# 10X_SD_CARD_READER_SCH_SHEET_2.net
KiCad netlist of a schematic drawn in Altium Designer
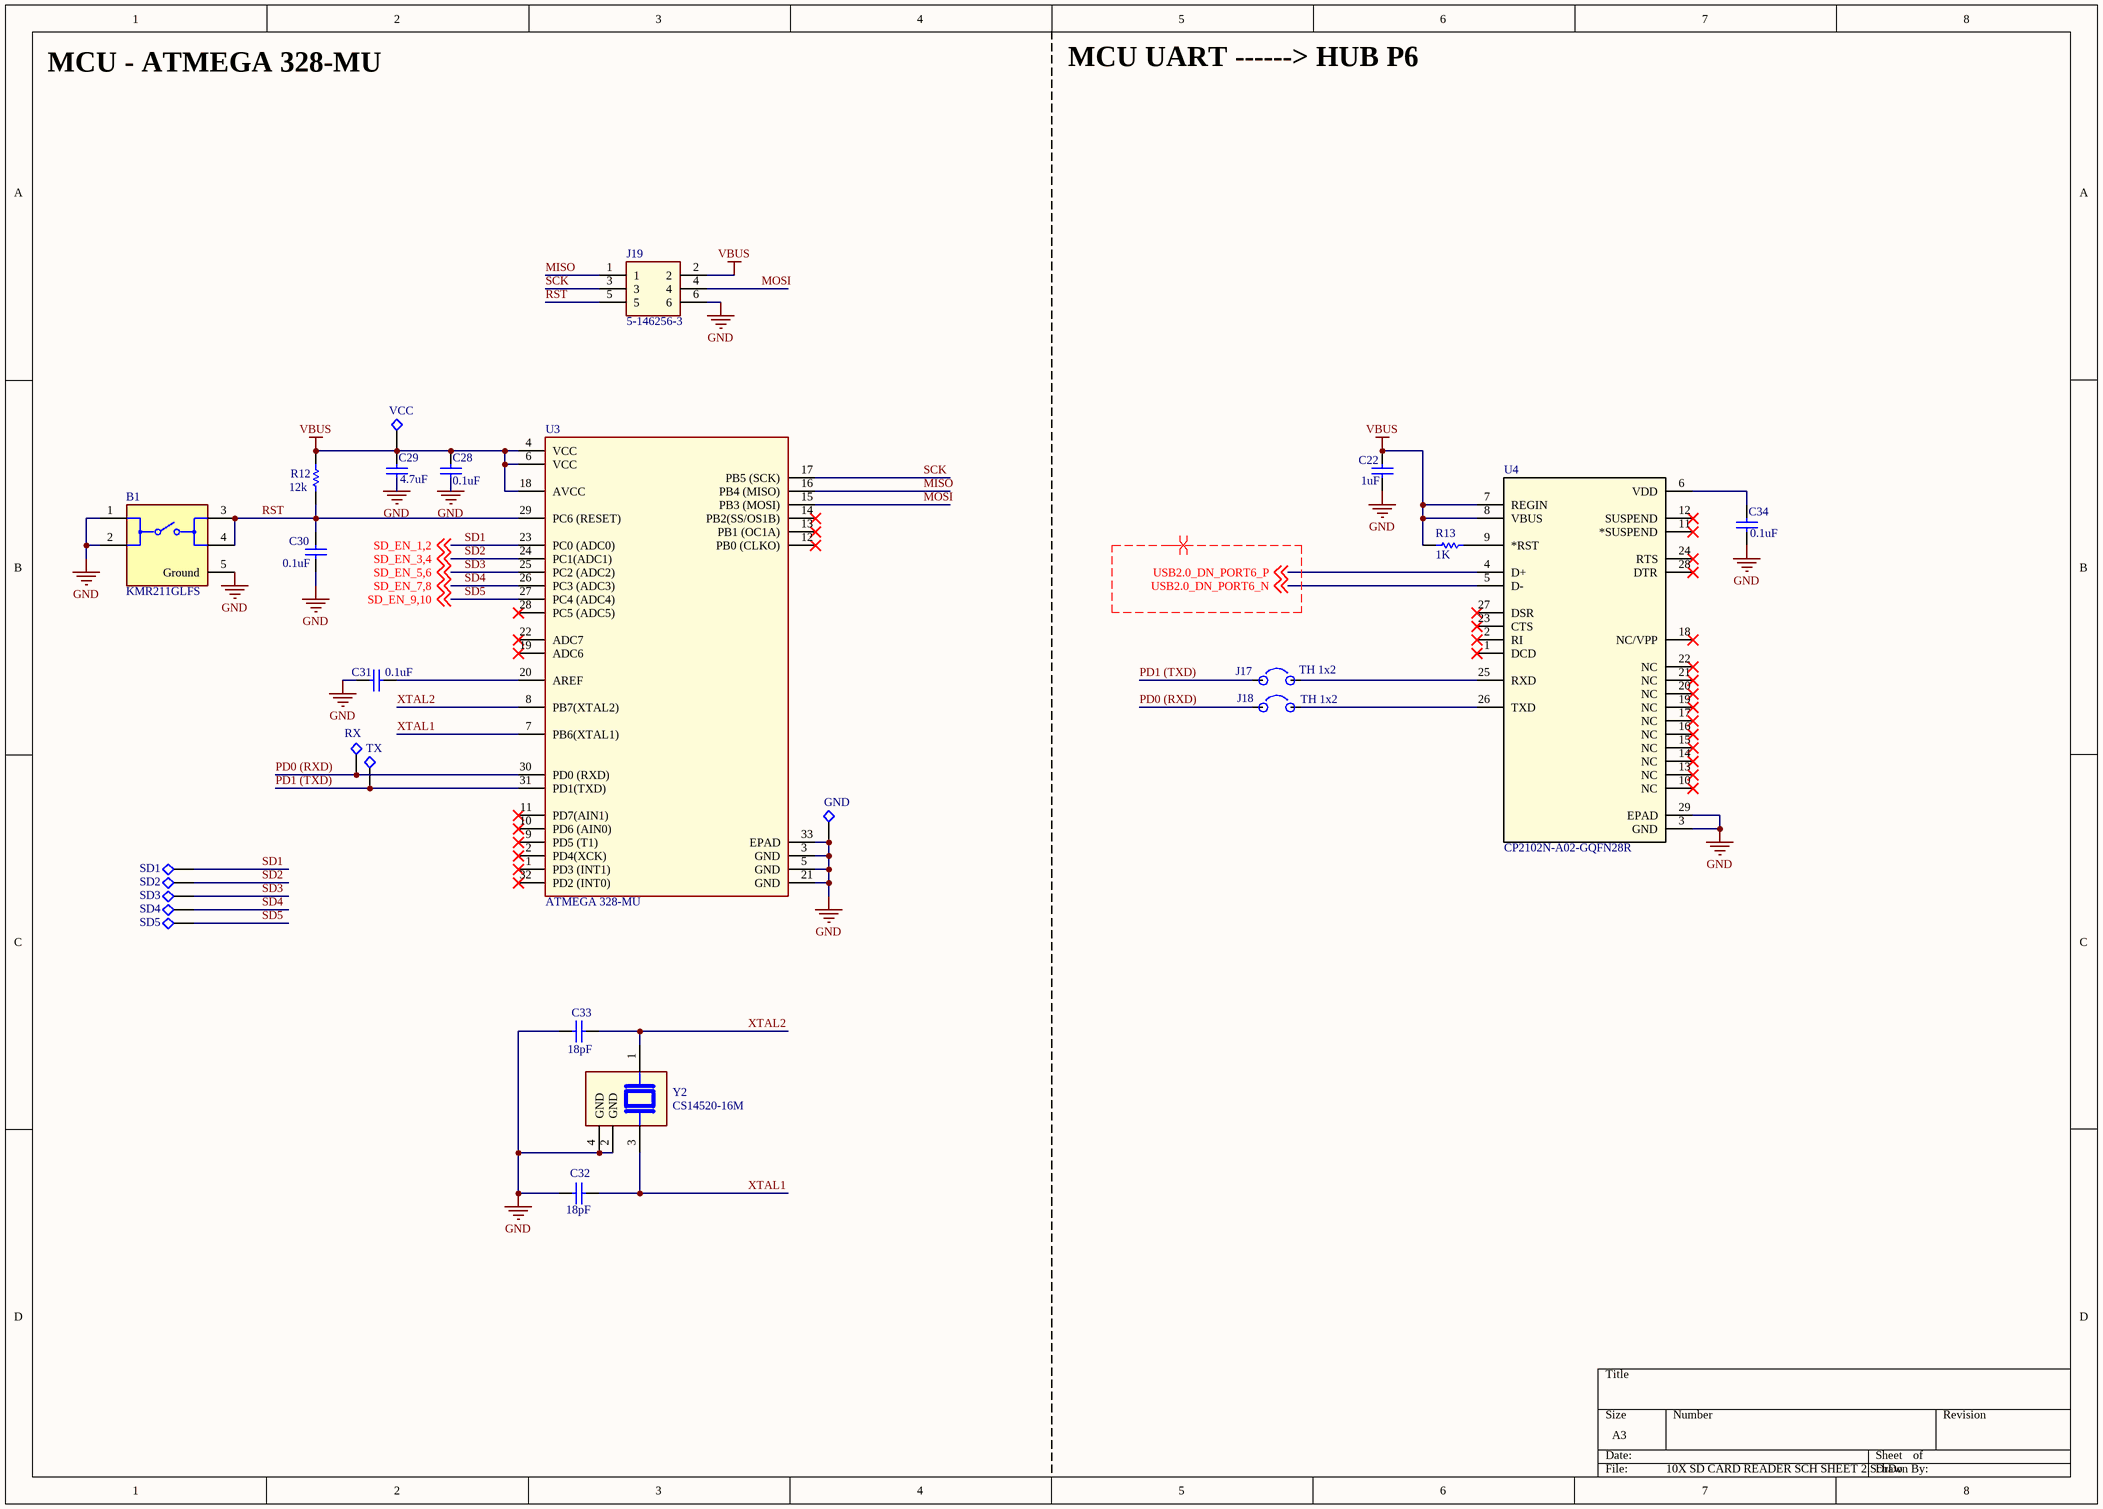
[diagram p0: 10X SD CARD READER SCH SHEET 2.SchDoc]

(export (version "E")
  (design (tool "Eeschema 10.0.6"))
  (components
    (comp (ref "B1")
      (value "KMR211GLFS")
      (footprint "FP-KMR211GLFS-MFG")
      (description "SWITCH TACTILE SPST-NO 0.05A 32V")
      (libsource (lib "Altium Content Vault") (part "99988cc0f9d3d39bd794ae22da860e5"))
    )
    (comp (ref "C22")
      (value "1uF")
      (footprint "C-0402/1005")
      (description "Capacitor")
      (fields (field (name "PUBLISHER") "Altium Limited"))
      (libsource (lib "Miscellaneous Devices") (part "Cap"))
    )
    (comp (ref "C28")
      (value "0.1uF")
      (footprint "C-0402/1005")
      (description "Capacitor")
      (fields (field (name "PUBLISHER") "Altium Limited"))
      (libsource (lib "Miscellaneous Devices") (part "Cap"))
    )
    (comp (ref "C29")
      (value "4.7uF")
      (footprint "0805-CAP")
      (description "Capacitor")
      (fields (field (name "PUBLISHER") "Altium Limited"))
      (libsource (lib "Miscellaneous Devices") (part "Cap"))
    )
    (comp (ref "C30")
      (value "0.1uF")
      (footprint "C-0402/1005")
      (description "Capacitor")
      (fields (field (name "PUBLISHER") "Altium Limited"))
      (libsource (lib "Miscellaneous Devices") (part "Cap"))
    )
    (comp (ref "C31")
      (value "0.1uF")
      (footprint "C-0402/1005")
      (description "Capacitor")
      (fields (field (name "PUBLISHER") "Altium Limited"))
      (libsource (lib "Miscellaneous Devices") (part "Cap"))
    )
    (comp (ref "C32")
      (value "18pF")
      (footprint "C-0402/1005")
      (description "Capacitor")
      (fields (field (name "PUBLISHER") "Altium Limited"))
      (libsource (lib "Miscellaneous Devices") (part "Cap"))
    )
    (comp (ref "C33")
      (value "18pF")
      (footprint "C-0402/1005")
      (description "Capacitor")
      (fields (field (name "PUBLISHER") "Altium Limited"))
      (libsource (lib "Miscellaneous Devices") (part "Cap"))
    )
    (comp (ref "C34")
      (value "0.1uF")
      (footprint "C-0402/1005")
      (description "Capacitor")
      (fields (field (name "PUBLISHER") "Altium Limited"))
      (libsource (lib "Miscellaneous Devices") (part "Cap"))
    )
    (comp (ref "GND")
      (value "Test Points")
      (footprint "Test Point TH Round H0.9,D1.6")
      (libsource (lib "Custom_Library") (part "Test Points"))
    )
    (comp (ref "J17")
      (value "TH 1x2")
      (footprint "PIN HEADER 1x2 2.54mm")
      (description "CONN HEADER VERT 3POS 2.54MM")
      (fields (field (name "MFR. PART NO.") "75160-156-03LF"))
      (libsource (lib "Custom_Library") (part "Jumper 2 pin"))
    )
    (comp (ref "J18")
      (value "TH 1x2")
      (footprint "PIN HEADER 1x2 2.54mm")
      (description "CONN HEADER VERT 3POS 2.54MM")
      (fields (field (name "MFR. PART NO.") "75160-156-03LF"))
      (libsource (lib "Custom_Library") (part "Jumper 2 pin"))
    )
    (comp (ref "J19")
      (value "5-146256-3")
      (footprint "TE_5-146256-3")
      (description "Header; Breakaway; 0.100 x 0.100 in.; PC Board; Dual; 6; 0.025 in.; 0.12 in.")
      (fields (field (name "MF") "TE Connectivity") (field (name "DIGI-KEY_PART_NUMBER") "A121369-ND"))
      (libsource (lib "SnapEDAsch") (part "5-146256-3"))
    )
    (comp (ref "R12")
      (value "12k")
      (footprint "R-0402/1005")
      (description "Resistor")
      (fields (field (name "PUBLISHER") "Altium Limited"))
      (libsource (lib "Miscellaneous Devices") (part "Res1"))
    )
    (comp (ref "R13")
      (value "1K")
      (footprint "R-0402/1005")
      (description "Resistor")
      (fields (field (name "PUBLISHER") "Altium Limited"))
      (libsource (lib "Miscellaneous Devices") (part "Res1"))
    )
    (comp (ref "RX")
      (value "Test Points")
      (footprint "Test Point TH Round H0.9,D1.6")
      (libsource (lib "Custom_Library") (part "Test Points"))
    )
    (comp (ref "SD1")
      (value "Test Points")
      (footprint "Test Point TH Round H0.9,D1.6")
      (libsource (lib "Custom_Library") (part "Test Points"))
    )
    (comp (ref "SD2")
      (value "Test Points")
      (footprint "Test Point TH Round H0.9,D1.6")
      (libsource (lib "Custom_Library") (part "Test Points"))
    )
    (comp (ref "SD3")
      (value "Test Points")
      (footprint "Test Point TH Round H0.9,D1.6")
      (libsource (lib "Custom_Library") (part "Test Points"))
    )
    (comp (ref "SD4")
      (value "Test Points")
      (footprint "Test Point TH Round H0.9,D1.6")
      (libsource (lib "Custom_Library") (part "Test Points"))
    )
    (comp (ref "SD5")
      (value "Test Points")
      (footprint "Test Point TH Round H0.9,D1.6")
      (libsource (lib "Custom_Library") (part "Test Points"))
    )
    (comp (ref "TX")
      (value "Test Points")
      (footprint "Test Point TH Round H0.9,D1.6")
      (libsource (lib "Custom_Library") (part "Test Points"))
    )
    (comp (ref "U3")
      (value "ATMEGA 328-MU")
      (footprint "ATMEGA 328P")
      (description "IC MCU 8BIT 32KB FLASH 32VQFN")
      (fields
        (field (name "MANUFACTURER") "Microchip Technology")
        (field (name "DIGI-KEY PART NUMBER") "ATMEGA328P-MU-ND")
      )
      (libsource (lib "10X SD CARD READER SCH LIB") (part "ATMEGA 328-MU"))
    )
    (comp (ref "U4")
      (value "CP2102N-A02-GQFN28R")
      (footprint "CP2102")
      (description "USB Bridge, USB to UART USB 2.0 UART Interface")
      (fields
        (field (name "MANUFACTURER") "Silicon Labs")
        (field (name "DIGI-KEY PART NUMBER") "336-5890-2-ND")
      )
      (libsource (lib "10X SD CARD READER SCH LIB") (part "CP2102"))
    )
    (comp (ref "VCC")
      (value "Test Points")
      (footprint "Test Point TH Round H0.9,D1.6")
      (libsource (lib "Custom_Library") (part "Test Points"))
    )
    (comp (ref "Y2")
      (value "CS14520-16M")
      (footprint "FL1600044")
      (libsource (lib "10X SD CARD READER SCH LIB") (part "FL1600044"))
    )
  )
  (nets
    (net (code "1") (name "/MISO") (class "Default")
      (node (ref "J19") (pin "1") (pinfunction "1_1") (pintype "passive"))
      (node (ref "U3") (pin "16") (pinfunction "PB4_(MISO)_16") (pintype "passive"))
    )
    (net (code "2") (name "/MOSI") (class "Default")
      (node (ref "J19") (pin "4") (pinfunction "4_4") (pintype "passive"))
      (node (ref "U3") (pin "15") (pinfunction "PB3_(MOSI)_15") (pintype "passive"))
    )
    (net (code "3") (name "/PD0 (RXD)") (class "Default")
      (node (ref "J18") (pin "1") (pinfunction "1_1") (pintype "passive"))
      (node (ref "RX") (pin "1") (pinfunction "1_1") (pintype "passive"))
      (node (ref "U3") (pin "30") (pinfunction "PD0_(RXD)_30") (pintype "passive"))
    )
    (net (code "4") (name "/PD1 (TXD)") (class "Default")
      (node (ref "J17") (pin "1") (pinfunction "1_1") (pintype "passive"))
      (node (ref "TX") (pin "1") (pinfunction "1_1") (pintype "passive"))
      (node (ref "U3") (pin "31") (pinfunction "PD1(TXD)_31") (pintype "passive"))
    )
    (net (code "5") (name "/RST") (class "Default")
      (node (ref "B1") (pin "3") (pinfunction "3_3") (pintype "passive"))
      (node (ref "B1") (pin "4") (pinfunction "4_4") (pintype "passive"))
      (node (ref "C30") (pin "2") (pinfunction "2_2") (pintype "passive"))
      (node (ref "J19") (pin "5") (pinfunction "5_5") (pintype "passive"))
      (node (ref "R12") (pin "2") (pinfunction "2_2") (pintype "passive"))
      (node (ref "U3") (pin "29") (pinfunction "PC6_(RESET)_29") (pintype "passive"))
    )
    (net (code "6") (name "/SCK") (class "Default")
      (node (ref "J19") (pin "3") (pinfunction "3_3") (pintype "passive"))
      (node (ref "U3") (pin "17") (pinfunction "PB5_(SCK)_17") (pintype "passive"))
    )
    (net (code "7") (name "/XTAL1") (class "Default")
      (node (ref "C32") (pin "1") (pinfunction "1_1") (pintype "passive"))
      (node (ref "U3") (pin "7") (pinfunction "PB6(XTAL1)_7") (pintype "passive"))
      (node (ref "Y2") (pin "3") (pinfunction "2_3") (pintype "passive"))
    )
    (net (code "8") (name "/XTAL2") (class "Default")
      (node (ref "C33") (pin "1") (pinfunction "1_1") (pintype "passive"))
      (node (ref "U3") (pin "8") (pinfunction "PB7(XTAL2)_8") (pintype "passive"))
      (node (ref "Y2") (pin "1") (pinfunction "1_1") (pintype "passive"))
    )
    (net (code "9") (name "GND") (class "Default")
      (node (ref "B1") (pin "1") (pinfunction "1_1") (pintype "passive"))
      (node (ref "B1") (pin "2") (pinfunction "2_2") (pintype "passive"))
      (node (ref "B1") (pin "5") (pinfunction "Ground_5") (pintype "power_in"))
      (node (ref "C22") (pin "2") (pinfunction "2_2") (pintype "passive"))
      (node (ref "C28") (pin "2") (pinfunction "2_2") (pintype "passive"))
      (node (ref "C29") (pin "2") (pinfunction "2_2") (pintype "passive"))
      (node (ref "C30") (pin "1") (pinfunction "1_1") (pintype "passive"))
      (node (ref "C31") (pin "1") (pinfunction "1_1") (pintype "passive"))
      (node (ref "C32") (pin "2") (pinfunction "2_2") (pintype "passive"))
      (node (ref "C33") (pin "2") (pinfunction "2_2") (pintype "passive"))
      (node (ref "C34") (pin "2") (pinfunction "2_2") (pintype "passive"))
      (node (ref "GND") (pin "1") (pinfunction "1_1") (pintype "passive"))
      (node (ref "J19") (pin "6") (pinfunction "6_6") (pintype "passive"))
      (node (ref "U3") (pin "21") (pinfunction "GND_21") (pintype "passive"))
      (node (ref "U3") (pin "3") (pinfunction "GND_3") (pintype "passive"))
      (node (ref "U3") (pin "33") (pinfunction "EPAD_33") (pintype "passive"))
      (node (ref "U3") (pin "5") (pinfunction "GND_5") (pintype "passive"))
      (node (ref "U4") (pin "29") (pinfunction "EPAD_29") (pintype "passive"))
      (node (ref "U4") (pin "3") (pinfunction "GND_3") (pintype "passive"))
      (node (ref "Y2") (pin "2") (pinfunction "GND_2") (pintype "power_in"))
      (node (ref "Y2") (pin "4") (pinfunction "GND_4") (pintype "power_in"))
    )
    (net (code "10") (name "Net-(U3-AREF)") (class "Default")
      (node (ref "C31") (pin "2") (pinfunction "2_2") (pintype "passive"))
      (node (ref "U3") (pin "20") (pinfunction "AREF_20") (pintype "passive"))
    )
    (net (code "11") (name "Net-(U4-*RST)") (class "Default")
      (node (ref "R13") (pin "2") (pinfunction "2_2") (pintype "passive"))
      (node (ref "U4") (pin "9") (pinfunction "*RST_9") (pintype "passive"))
    )
    (net (code "12") (name "Net-(U4-RXD)") (class "Default")
      (node (ref "J17") (pin "2") (pinfunction "2_2") (pintype "passive"))
      (node (ref "U4") (pin "25") (pinfunction "RXD_25") (pintype "passive"))
    )
    (net (code "13") (name "Net-(U4-TXD)") (class "Default")
      (node (ref "J18") (pin "2") (pinfunction "2_2") (pintype "passive"))
      (node (ref "U4") (pin "26") (pinfunction "TXD_26") (pintype "passive"))
    )
    (net (code "14") (name "Net-(U4-VDD)") (class "Default")
      (node (ref "C34") (pin "1") (pinfunction "1_1") (pintype "passive"))
      (node (ref "U4") (pin "6") (pinfunction "VDD_6") (pintype "passive"))
    )
    (net (code "15") (name "SD_EN_1,2") (class "Default")
      (node (ref "SD1") (pin "1") (pinfunction "1_1") (pintype "passive"))
      (node (ref "U3") (pin "23") (pinfunction "PC0_(ADC0)_23") (pintype "passive"))
    )
    (net (code "16") (name "SD_EN_3,4") (class "Default")
      (node (ref "SD2") (pin "1") (pinfunction "1_1") (pintype "passive"))
      (node (ref "U3") (pin "24") (pinfunction "PC1(ADC1)_24") (pintype "passive"))
    )
    (net (code "17") (name "SD_EN_5,6") (class "Default")
      (node (ref "SD3") (pin "1") (pinfunction "1_1") (pintype "passive"))
      (node (ref "U3") (pin "25") (pinfunction "PC2_(ADC2)_25") (pintype "passive"))
    )
    (net (code "18") (name "SD_EN_7,8") (class "Default")
      (node (ref "SD4") (pin "1") (pinfunction "1_1") (pintype "passive"))
      (node (ref "U3") (pin "26") (pinfunction "PC3_(ADC3)_26") (pintype "passive"))
    )
    (net (code "19") (name "SD_EN_9,10") (class "Default")
      (node (ref "SD5") (pin "1") (pinfunction "1_1") (pintype "passive"))
      (node (ref "U3") (pin "27") (pinfunction "PC4_(ADC4)_27") (pintype "passive"))
    )
    (net (code "20") (name "USB2.0_DN_PORT6_N") (class "Default")
      (node (ref "U4") (pin "5") (pinfunction "D-_5") (pintype "passive"))
    )
    (net (code "21") (name "USB2.0_DN_PORT6_P") (class "Default")
      (node (ref "U4") (pin "4") (pinfunction "D+_4") (pintype "passive"))
    )
    (net (code "22") (name "VBUS") (class "Default")
      (node (ref "C22") (pin "1") (pinfunction "1_1") (pintype "passive"))
      (node (ref "C28") (pin "1") (pinfunction "1_1") (pintype "passive"))
      (node (ref "C29") (pin "1") (pinfunction "1_1") (pintype "passive"))
      (node (ref "J19") (pin "2") (pinfunction "2_2") (pintype "passive"))
      (node (ref "R12") (pin "1") (pinfunction "1_1") (pintype "passive"))
      (node (ref "R13") (pin "1") (pinfunction "1_1") (pintype "passive"))
      (node (ref "U3") (pin "18") (pinfunction "AVCC_18") (pintype "passive"))
      (node (ref "U3") (pin "4") (pinfunction "VCC_4") (pintype "passive"))
      (node (ref "U3") (pin "6") (pinfunction "VCC_6") (pintype "passive"))
      (node (ref "U4") (pin "7") (pinfunction "REGIN_7") (pintype "passive"))
      (node (ref "U4") (pin "8") (pinfunction "VBUS_8") (pintype "passive"))
      (node (ref "VCC") (pin "1") (pinfunction "1_1") (pintype "passive"))
    )
    (net (code "23") (name "unconnected-(U3-ADC6-Pad19)") (class "Default")
      (node (ref "U3") (pin "19") (pinfunction "ADC6_19") (pintype "passive+no_connect"))
    )
    (net (code "24") (name "unconnected-(U3-ADC7-Pad22)") (class "Default")
      (node (ref "U3") (pin "22") (pinfunction "ADC7_22") (pintype "passive+no_connect"))
    )
    (net (code "25") (name "unconnected-(U3-PB0_(CLKO)-Pad12)") (class "Default")
      (node (ref "U3") (pin "12") (pinfunction "PB0_(CLKO)_12") (pintype "passive+no_connect"))
    )
    (net (code "26") (name "unconnected-(U3-PB1_(OC1A)-Pad13)") (class "Default")
      (node (ref "U3") (pin "13") (pinfunction "PB1_(OC1A)_13") (pintype "passive+no_connect"))
    )
    (net (code "27") (name "unconnected-(U3-PB2(SS{slash}OS1B)-Pad14)") (class "Default")
      (node (ref "U3") (pin "14") (pinfunction "PB2(SS/OS1B)_14") (pintype "passive+no_connect"))
    )
    (net (code "28") (name "unconnected-(U3-PC5_(ADC5)-Pad28)") (class "Default")
      (node (ref "U3") (pin "28") (pinfunction "PC5_(ADC5)_28") (pintype "passive+no_connect"))
    )
    (net (code "29") (name "unconnected-(U3-PD2_(INT0)-Pad32)") (class "Default")
      (node (ref "U3") (pin "32") (pinfunction "PD2_(INT0)_32") (pintype "passive+no_connect"))
    )
    (net (code "30") (name "unconnected-(U3-PD3_(INT1)-Pad1)") (class "Default")
      (node (ref "U3") (pin "1") (pinfunction "PD3_(INT1)_1") (pintype "passive+no_connect"))
    )
    (net (code "31") (name "unconnected-(U3-PD4(XCK)-Pad2)") (class "Default")
      (node (ref "U3") (pin "2") (pinfunction "PD4(XCK)_2") (pintype "passive+no_connect"))
    )
    (net (code "32") (name "unconnected-(U3-PD5_(T1)-Pad9)") (class "Default")
      (node (ref "U3") (pin "9") (pinfunction "PD5_(T1)_9") (pintype "passive+no_connect"))
    )
    (net (code "33") (name "unconnected-(U3-PD6_(AIN0)-Pad10)") (class "Default")
      (node (ref "U3") (pin "10") (pinfunction "PD6_(AIN0)_10") (pintype "passive+no_connect"))
    )
    (net (code "34") (name "unconnected-(U3-PD7(AIN1)-Pad11)") (class "Default")
      (node (ref "U3") (pin "11") (pinfunction "PD7(AIN1)_11") (pintype "passive+no_connect"))
    )
    (net (code "35") (name "unconnected-(U4-*SUSPEND-Pad11)") (class "Default")
      (node (ref "U4") (pin "11") (pinfunction "*SUSPEND_11") (pintype "passive+no_connect"))
    )
    (net (code "36") (name "unconnected-(U4-CTS-Pad23)") (class "Default")
      (node (ref "U4") (pin "23") (pinfunction "CTS_23") (pintype "passive+no_connect"))
    )
    (net (code "37") (name "unconnected-(U4-DCD-Pad1)") (class "Default")
      (node (ref "U4") (pin "1") (pinfunction "DCD_1") (pintype "passive+no_connect"))
    )
    (net (code "38") (name "unconnected-(U4-DSR-Pad27)") (class "Default")
      (node (ref "U4") (pin "27") (pinfunction "DSR_27") (pintype "passive+no_connect"))
    )
    (net (code "39") (name "unconnected-(U4-DTR-Pad28)") (class "Default")
      (node (ref "U4") (pin "28") (pinfunction "DTR_28") (pintype "passive+no_connect"))
    )
    (net (code "40") (name "unconnected-(U4-NC-Pad10)") (class "Default")
      (node (ref "U4") (pin "10") (pinfunction "NC_10") (pintype "passive+no_connect"))
    )
    (net (code "41") (name "unconnected-(U4-NC-Pad13)") (class "Default")
      (node (ref "U4") (pin "13") (pinfunction "NC_13") (pintype "passive+no_connect"))
    )
    (net (code "42") (name "unconnected-(U4-NC-Pad14)") (class "Default")
      (node (ref "U4") (pin "14") (pinfunction "NC_14") (pintype "passive+no_connect"))
    )
    (net (code "43") (name "unconnected-(U4-NC-Pad15)") (class "Default")
      (node (ref "U4") (pin "15") (pinfunction "NC_15") (pintype "passive+no_connect"))
    )
    (net (code "44") (name "unconnected-(U4-NC-Pad16)") (class "Default")
      (node (ref "U4") (pin "16") (pinfunction "NC_16") (pintype "passive+no_connect"))
    )
    (net (code "45") (name "unconnected-(U4-NC-Pad17)") (class "Default")
      (node (ref "U4") (pin "17") (pinfunction "NC_17") (pintype "passive+no_connect"))
    )
    (net (code "46") (name "unconnected-(U4-NC-Pad19)") (class "Default")
      (node (ref "U4") (pin "19") (pinfunction "NC_19") (pintype "passive+no_connect"))
    )
    (net (code "47") (name "unconnected-(U4-NC-Pad20)") (class "Default")
      (node (ref "U4") (pin "20") (pinfunction "NC_20") (pintype "passive+no_connect"))
    )
    (net (code "48") (name "unconnected-(U4-NC-Pad21)") (class "Default")
      (node (ref "U4") (pin "21") (pinfunction "NC_21") (pintype "passive+no_connect"))
    )
    (net (code "49") (name "unconnected-(U4-NC-Pad22)") (class "Default")
      (node (ref "U4") (pin "22") (pinfunction "NC_22") (pintype "passive+no_connect"))
    )
    (net (code "50") (name "unconnected-(U4-NC{slash}VPP-Pad18)") (class "Default")
      (node (ref "U4") (pin "18") (pinfunction "NC/VPP_18") (pintype "passive+no_connect"))
    )
    (net (code "51") (name "unconnected-(U4-RI-Pad2)") (class "Default")
      (node (ref "U4") (pin "2") (pinfunction "RI_2") (pintype "passive+no_connect"))
    )
    (net (code "52") (name "unconnected-(U4-RTS-Pad24)") (class "Default")
      (node (ref "U4") (pin "24") (pinfunction "RTS_24") (pintype "passive+no_connect"))
    )
    (net (code "53") (name "unconnected-(U4-SUSPEND-Pad12)") (class "Default")
      (node (ref "U4") (pin "12") (pinfunction "SUSPEND_12") (pintype "passive+no_connect"))
    )
  )
)
